# untitled.net
KiCad netlist of a schematic drawn in EAGLE
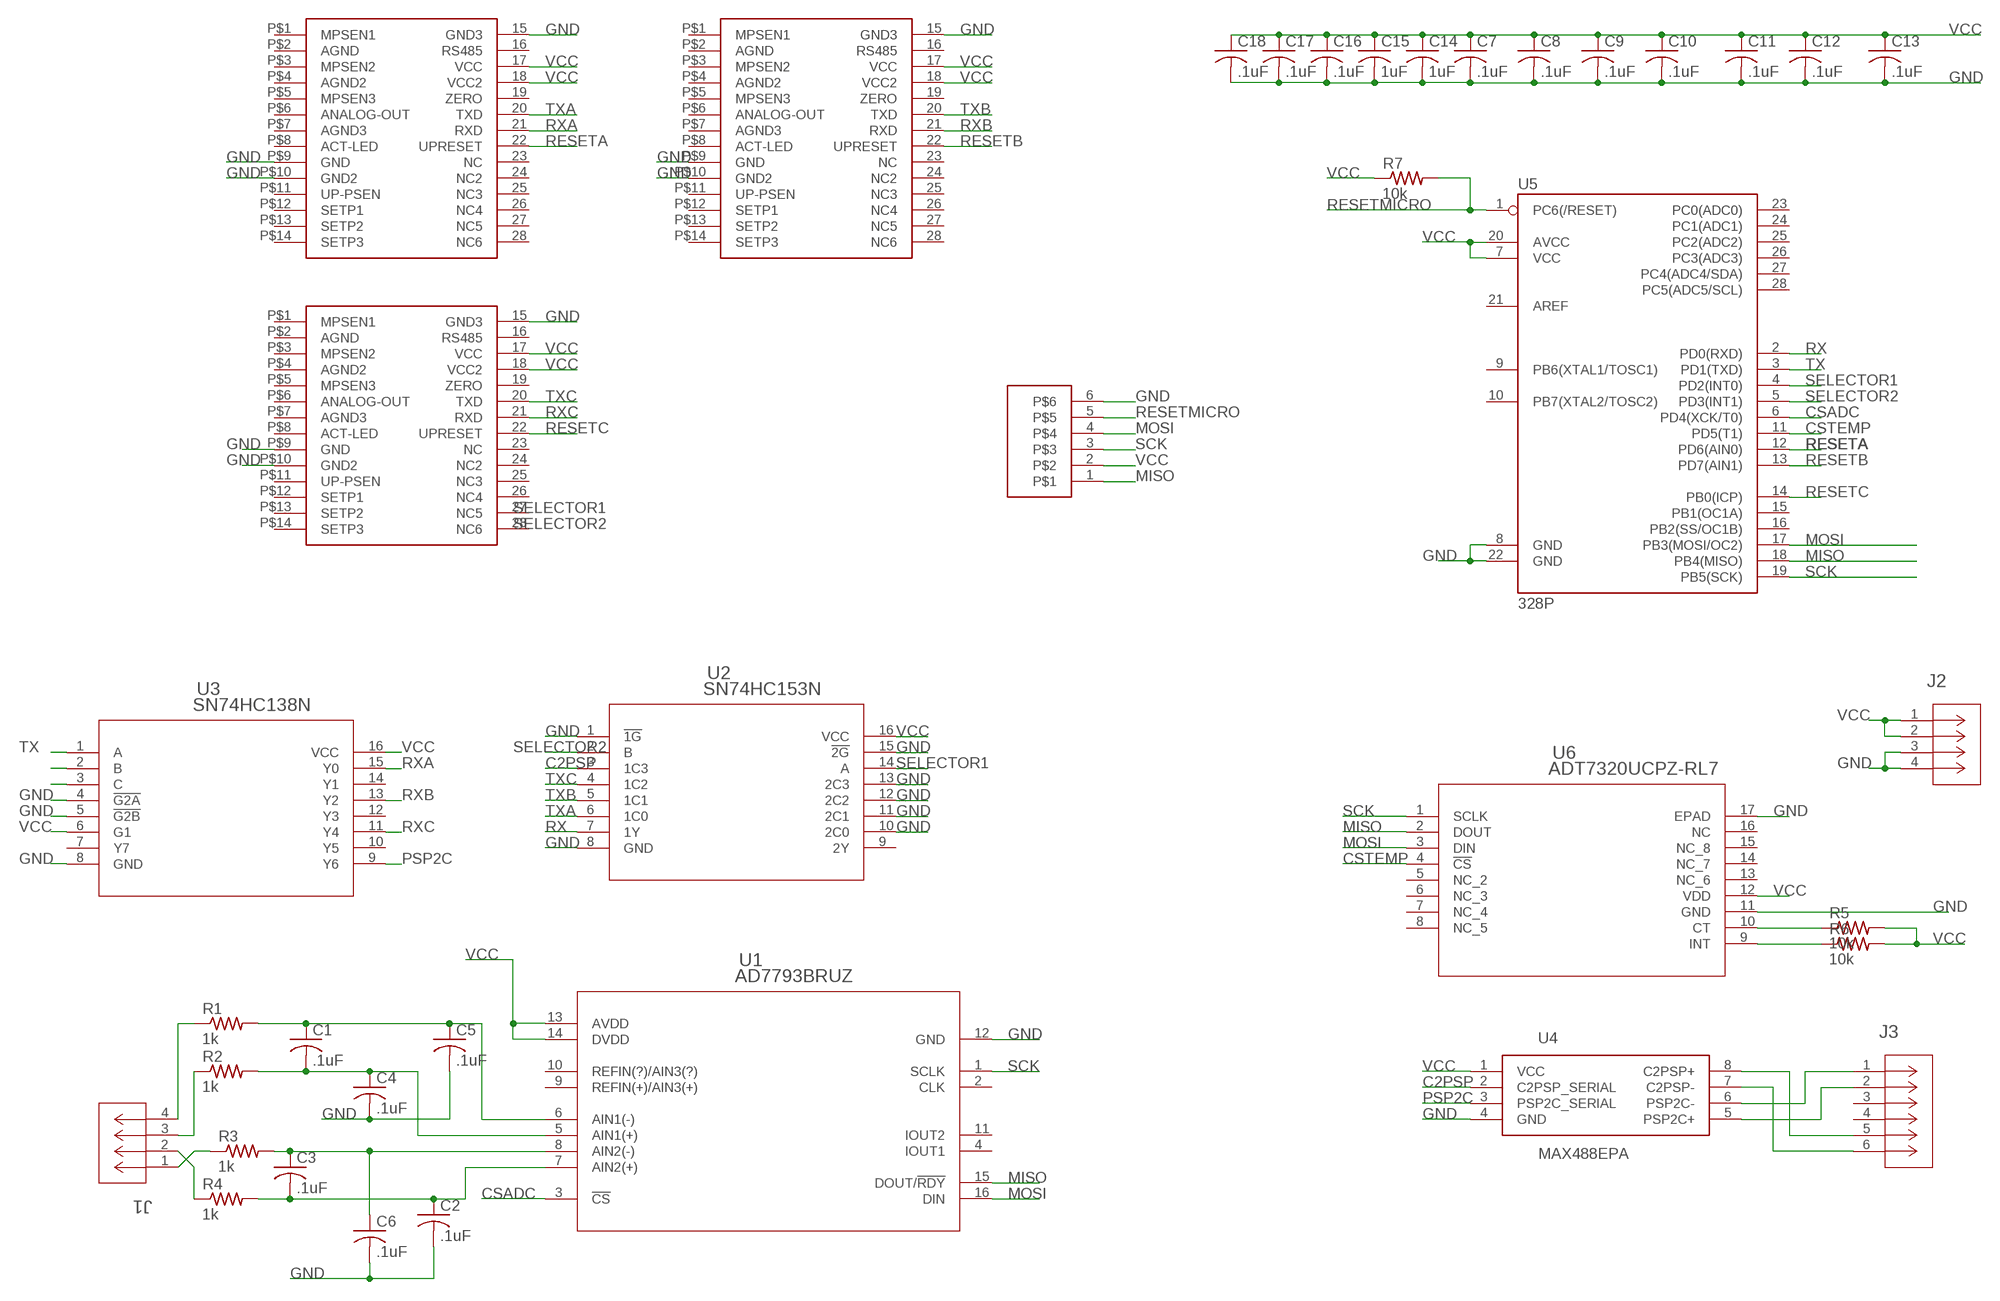
[diagram p0: schematic, sheet 1]

(export (version "E")
  (design (tool "Eeschema 10.0.6"))
  (components
    (comp (ref "C1")
      (value ".1uF")
      (footprint "eagle-import:C0603")
      (libsource (lib "eagle-import") (part "C-USC0603"))
    )
    (comp (ref "C2")
      (value ".1uF")
      (footprint "eagle-import:C0603")
      (libsource (lib "eagle-import") (part "C-USC0603"))
    )
    (comp (ref "C3")
      (value ".1uF")
      (footprint "eagle-import:C0603")
      (libsource (lib "eagle-import") (part "C-USC0603"))
    )
    (comp (ref "C4")
      (value ".1uF")
      (footprint "eagle-import:C0603")
      (libsource (lib "eagle-import") (part "C-USC0603"))
    )
    (comp (ref "C5")
      (value ".1uF")
      (footprint "eagle-import:C0603")
      (libsource (lib "eagle-import") (part "C-USC0603"))
    )
    (comp (ref "C6")
      (value ".1uF")
      (footprint "eagle-import:C0603")
      (libsource (lib "eagle-import") (part "C-USC0603"))
    )
    (comp (ref "C7")
      (value ".1uF")
      (footprint "eagle-import:C0603")
      (libsource (lib "eagle-import") (part "C-USC0603"))
    )
    (comp (ref "C8")
      (value ".1uF")
      (footprint "eagle-import:C0603")
      (libsource (lib "eagle-import") (part "C-USC0603"))
    )
    (comp (ref "C9")
      (value ".1uF")
      (footprint "eagle-import:C0603")
      (libsource (lib "eagle-import") (part "C-USC0603"))
    )
    (comp (ref "C10")
      (value ".1uF")
      (footprint "eagle-import:C0603")
      (libsource (lib "eagle-import") (part "C-USC0603"))
    )
    (comp (ref "C11")
      (value ".1uF")
      (footprint "eagle-import:C0603")
      (libsource (lib "eagle-import") (part "C-USC0603"))
    )
    (comp (ref "C12")
      (value ".1uF")
      (footprint "eagle-import:C0603")
      (libsource (lib "eagle-import") (part "C-USC0603"))
    )
    (comp (ref "C13")
      (value ".1uF")
      (footprint "eagle-import:C0603")
      (libsource (lib "eagle-import") (part "C-USC0603"))
    )
    (comp (ref "C14")
      (value "1uF")
      (footprint "eagle-import:C1206")
      (libsource (lib "eagle-import") (part "C-USC1206"))
    )
    (comp (ref "C15")
      (value "1uF")
      (footprint "eagle-import:C1206")
      (libsource (lib "eagle-import") (part "C-USC1206"))
    )
    (comp (ref "C16")
      (value ".1uF")
      (footprint "eagle-import:C0603")
      (libsource (lib "eagle-import") (part "C-USC0603"))
    )
    (comp (ref "C17")
      (value ".1uF")
      (footprint "eagle-import:C0603")
      (libsource (lib "eagle-import") (part "C-USC0603"))
    )
    (comp (ref "C18")
      (value ".1uF")
      (footprint "eagle-import:C0603")
      (libsource (lib "eagle-import") (part "C-USC0603"))
    )
    (comp (ref "J1")
      (value "DF11-4")
      (footprint "eagle-import:DF11-4")
      (libsource (lib "eagle-import") (part "DF11-4"))
    )
    (comp (ref "J2")
      (value "DF11-4")
      (footprint "eagle-import:DF11-4")
      (libsource (lib "eagle-import") (part "DF11-4"))
    )
    (comp (ref "J3")
      (value "DF11-6DP-2DSA(01)")
      (footprint "eagle-import:CON6_2X3_UF_DF11")
      (libsource (lib "eagle-import") (part "DF11-6DP-2DSA(01)"))
    )
    (comp (ref "R1")
      (value "1k")
      (footprint "eagle-import:R0603")
      (libsource (lib "eagle-import") (part "R-US_R0603"))
    )
    (comp (ref "R2")
      (value "1k")
      (footprint "eagle-import:R0603")
      (libsource (lib "eagle-import") (part "R-US_R0603"))
    )
    (comp (ref "R3")
      (value "1k")
      (footprint "eagle-import:R0603")
      (libsource (lib "eagle-import") (part "R-US_R0603"))
    )
    (comp (ref "R4")
      (value "1k")
      (footprint "eagle-import:R0603")
      (libsource (lib "eagle-import") (part "R-US_R0603"))
    )
    (comp (ref "R5")
      (value "10k")
      (footprint "eagle-import:R0603")
      (libsource (lib "eagle-import") (part "R-US_R0603"))
    )
    (comp (ref "R6")
      (value "10k")
      (footprint "eagle-import:R0603")
      (libsource (lib "eagle-import") (part "R-US_R0603"))
    )
    (comp (ref "R7")
      (value "10k")
      (footprint "eagle-import:R0603")
      (libsource (lib "eagle-import") (part "R-US_R0603"))
    )
    (comp (ref "U$1")
      (value "PROGRAMMER")
      (footprint "eagle-import:PROGRAMMER")
      (libsource (lib "eagle-import") (part "PROGRAMMER"))
    )
    (comp (ref "U$2")
      (value "MKS-PIRANI")
      (footprint "eagle-import:28PIN")
      (libsource (lib "eagle-import") (part "MKS-PIRANI"))
    )
    (comp (ref "U$3")
      (value "MKS-PIRANI")
      (footprint "eagle-import:28PIN")
      (libsource (lib "eagle-import") (part "MKS-PIRANI"))
    )
    (comp (ref "U$4")
      (value "MKS-PIRANI")
      (footprint "eagle-import:28PIN")
      (libsource (lib "eagle-import") (part "MKS-PIRANI"))
    )
    (comp (ref "U1")
      (value "AD7793BRUZ")
      (footprint "eagle-import:RU_16")
      (libsource (lib "eagle-import") (part "AD7793BRUZ"))
    )
    (comp (ref "U2")
      (value "SN74HC153N")
      (footprint "eagle-import:N16")
      (libsource (lib "eagle-import") (part "SN74HC153N"))
    )
    (comp (ref "U3")
      (value "SN74HC138N")
      (footprint "eagle-import:N16")
      (libsource (lib "eagle-import") (part "SN74HC138N"))
    )
    (comp (ref "U4")
      (value "MAX488EPA")
      (footprint "eagle-import:DIL08")
      (libsource (lib "eagle-import") (part "MAX488EPA"))
    )
    (comp (ref "U5")
      (value "328P")
      (footprint "eagle-import:DIP28")
      (libsource (lib "eagle-import") (part "ATMEGA328P_PDIP"))
    )
    (comp (ref "U6")
      (value "ADT7320UCPZ-RL7")
      (footprint "eagle-import:CP_16_17")
      (fields (field (name "MANUFACTURER_PART_NUMBER") "ADT7320UCPZRL7"))
      (libsource (lib "eagle-import") (part "ADT7320UCPZ-RL7"))
    )
  )
  (nets
    (net (code "1") (name "/C2PSP") (class "Default")
      (node (ref "U2") (pin "3") (pinfunction "1C3_3") (pintype "input"))
      (node (ref "U4") (pin "2") (pinfunction "C2PSP_SERIAL_2") (pintype "bidirectional"))
    )
    (net (code "2") (name "/CSADC") (class "Default")
      (node (ref "U1") (pin "3") (pinfunction "~{CS}_3") (pintype "input"))
      (node (ref "U5") (pin "6") (pinfunction "PD4(XCK/T0)_6") (pintype "bidirectional"))
    )
    (net (code "3") (name "/CSTEMP") (class "Default")
      (node (ref "U5") (pin "11") (pinfunction "PD5(T1)_11") (pintype "bidirectional"))
      (node (ref "U6") (pin "4") (pinfunction "~{CS}_4") (pintype "input"))
    )
    (net (code "4") (name "/GND") (class "Default")
      (node (ref "C10") (pin "2") (pinfunction "2_2") (pintype "passive"))
      (node (ref "C11") (pin "2") (pinfunction "2_2") (pintype "passive"))
      (node (ref "C12") (pin "2") (pinfunction "2_2") (pintype "passive"))
      (node (ref "C13") (pin "2") (pinfunction "2_2") (pintype "passive"))
      (node (ref "C14") (pin "2") (pinfunction "2_2") (pintype "passive"))
      (node (ref "C15") (pin "2") (pinfunction "2_2") (pintype "passive"))
      (node (ref "C16") (pin "2") (pinfunction "2_2") (pintype "passive"))
      (node (ref "C17") (pin "2") (pinfunction "2_2") (pintype "passive"))
      (node (ref "C18") (pin "2") (pinfunction "2_2") (pintype "passive"))
      (node (ref "C2") (pin "2") (pinfunction "2_2") (pintype "passive"))
      (node (ref "C4") (pin "2") (pinfunction "2_2") (pintype "passive"))
      (node (ref "C5") (pin "2") (pinfunction "2_2") (pintype "passive"))
      (node (ref "C6") (pin "2") (pinfunction "2_2") (pintype "passive"))
      (node (ref "C7") (pin "2") (pinfunction "2_2") (pintype "passive"))
      (node (ref "C8") (pin "2") (pinfunction "2_2") (pintype "passive"))
      (node (ref "C9") (pin "2") (pinfunction "2_2") (pintype "passive"))
      (node (ref "J2") (pin "3") (pinfunction "3_3") (pintype "passive"))
      (node (ref "J2") (pin "4") (pinfunction "4_4") (pintype "passive"))
      (node (ref "U$1") (pin "6") (pinfunction "P$6_6") (pintype "bidirectional"))
      (node (ref "U$2") (pin "15") (pinfunction "GND3_15") (pintype "bidirectional"))
      (node (ref "U$2") (pin "P$10") (pinfunction "GND2_P$10") (pintype "bidirectional"))
      (node (ref "U$2") (pin "P$9") (pinfunction "GND_P$9") (pintype "bidirectional"))
      (node (ref "U$3") (pin "15") (pinfunction "GND3_15") (pintype "bidirectional"))
      (node (ref "U$3") (pin "P$10") (pinfunction "GND2_P$10") (pintype "bidirectional"))
      (node (ref "U$3") (pin "P$9") (pinfunction "GND_P$9") (pintype "bidirectional"))
      (node (ref "U$4") (pin "15") (pinfunction "GND3_15") (pintype "bidirectional"))
      (node (ref "U$4") (pin "P$10") (pinfunction "GND2_P$10") (pintype "bidirectional"))
      (node (ref "U$4") (pin "P$9") (pinfunction "GND_P$9") (pintype "bidirectional"))
      (node (ref "U1") (pin "12") (pinfunction "GND_12") (pintype "passive"))
      (node (ref "U2") (pin "1") (pinfunction "~{1G}_1") (pintype "input"))
      (node (ref "U2") (pin "10") (pinfunction "2C0_10") (pintype "input"))
      (node (ref "U2") (pin "11") (pinfunction "2C1_11") (pintype "input"))
      (node (ref "U2") (pin "12") (pinfunction "2C2_12") (pintype "input"))
      (node (ref "U2") (pin "13") (pinfunction "2C3_13") (pintype "input"))
      (node (ref "U2") (pin "15") (pinfunction "~{2G}_15") (pintype "input"))
      (node (ref "U2") (pin "8") (pinfunction "GND_8") (pintype "power_in"))
      (node (ref "U3") (pin "4") (pinfunction "~{G2A}_4") (pintype "input"))
      (node (ref "U3") (pin "5") (pinfunction "~{G2B}_5") (pintype "input"))
      (node (ref "U3") (pin "8") (pinfunction "GND_8") (pintype "power_in"))
      (node (ref "U4") (pin "4") (pinfunction "GND_4") (pintype "bidirectional"))
      (node (ref "U5") (pin "22") (pinfunction "GND_22") (pintype "bidirectional"))
      (node (ref "U5") (pin "8") (pinfunction "GND_8") (pintype "bidirectional"))
      (node (ref "U6") (pin "11") (pinfunction "GND_11") (pintype "power_in"))
      (node (ref "U6") (pin "17") (pinfunction "EPAD_17") (pintype "passive"))
    )
    (net (code "5") (name "/MISO") (class "Default")
      (node (ref "U$1") (pin "1") (pinfunction "P$1_1") (pintype "bidirectional"))
      (node (ref "U1") (pin "15") (pinfunction "DOUT/~{RDY}_15") (pintype "output"))
      (node (ref "U5") (pin "18") (pinfunction "PB4(MISO)_18") (pintype "bidirectional"))
      (node (ref "U6") (pin "2") (pinfunction "DOUT_2") (pintype "output"))
    )
    (net (code "6") (name "/MOSI") (class "Default")
      (node (ref "U$1") (pin "4") (pinfunction "P$4_4") (pintype "bidirectional"))
      (node (ref "U1") (pin "16") (pinfunction "DIN_16") (pintype "input"))
      (node (ref "U5") (pin "17") (pinfunction "PB3(MOSI/OC2)_17") (pintype "bidirectional"))
      (node (ref "U6") (pin "3") (pinfunction "DIN_3") (pintype "input"))
    )
    (net (code "7") (name "/PSP2C") (class "Default")
      (node (ref "U3") (pin "9") (pinfunction "Y6_9") (pintype "output"))
      (node (ref "U4") (pin "3") (pinfunction "PSP2C_SERIAL_3") (pintype "bidirectional"))
    )
    (net (code "8") (name "/RESETA") (class "Default")
      (node (ref "U$2") (pin "22") (pinfunction "UPRESET_22") (pintype "bidirectional"))
      (node (ref "U5") (pin "12") (pinfunction "PD6(AIN0)_12") (pintype "bidirectional"))
    )
    (net (code "9") (name "/RESETB") (class "Default")
      (node (ref "U$4") (pin "22") (pinfunction "UPRESET_22") (pintype "bidirectional"))
      (node (ref "U5") (pin "13") (pinfunction "PD7(AIN1)_13") (pintype "bidirectional"))
    )
    (net (code "10") (name "/RESETC") (class "Default")
      (node (ref "U$3") (pin "22") (pinfunction "UPRESET_22") (pintype "bidirectional"))
      (node (ref "U5") (pin "14") (pinfunction "PB0(ICP)_14") (pintype "bidirectional"))
    )
    (net (code "11") (name "/RESETMICRO") (class "Default")
      (node (ref "R7") (pin "2") (pinfunction "2_2") (pintype "passive"))
      (node (ref "U$1") (pin "5") (pinfunction "P$5_5") (pintype "bidirectional"))
      (node (ref "U5") (pin "1") (pinfunction "PC6(/RESET)_1") (pintype "bidirectional"))
    )
    (net (code "12") (name "/RX") (class "Default")
      (node (ref "U2") (pin "7") (pinfunction "1Y_7") (pintype "passive"))
      (node (ref "U5") (pin "2") (pinfunction "PD0(RXD)_2") (pintype "bidirectional"))
    )
    (net (code "13") (name "/RXA") (class "Default")
      (node (ref "U$2") (pin "21") (pinfunction "RXD_21") (pintype "bidirectional"))
      (node (ref "U3") (pin "15") (pinfunction "Y0_15") (pintype "output"))
    )
    (net (code "14") (name "/RXB") (class "Default")
      (node (ref "U$4") (pin "21") (pinfunction "RXD_21") (pintype "bidirectional"))
      (node (ref "U3") (pin "13") (pinfunction "Y2_13") (pintype "output"))
    )
    (net (code "15") (name "/RXC") (class "Default")
      (node (ref "U$3") (pin "21") (pinfunction "RXD_21") (pintype "bidirectional"))
      (node (ref "U3") (pin "11") (pinfunction "Y4_11") (pintype "output"))
    )
    (net (code "16") (name "/SCK") (class "Default")
      (node (ref "U$1") (pin "3") (pinfunction "P$3_3") (pintype "bidirectional"))
      (node (ref "U1") (pin "1") (pinfunction "SCLK_1") (pintype "input"))
      (node (ref "U5") (pin "19") (pinfunction "PB5(SCK)_19") (pintype "bidirectional"))
      (node (ref "U6") (pin "1") (pinfunction "SCLK_1") (pintype "input"))
    )
    (net (code "17") (name "/SELECTOR1") (class "Default")
      (node (ref "U2") (pin "14") (pinfunction "A_14") (pintype "input"))
      (node (ref "U3") (pin "2") (pinfunction "B_2") (pintype "input"))
      (node (ref "U5") (pin "4") (pinfunction "PD2(INT0)_4") (pintype "bidirectional"))
    )
    (net (code "18") (name "/SELECTOR2") (class "Default")
      (node (ref "U2") (pin "2") (pinfunction "B_2") (pintype "input"))
      (node (ref "U3") (pin "3") (pinfunction "C_3") (pintype "input"))
      (node (ref "U5") (pin "5") (pinfunction "PD3(INT1)_5") (pintype "bidirectional"))
    )
    (net (code "19") (name "/TX") (class "Default")
      (node (ref "U3") (pin "1") (pinfunction "A_1") (pintype "input"))
      (node (ref "U5") (pin "3") (pinfunction "PD1(TXD)_3") (pintype "bidirectional"))
    )
    (net (code "20") (name "/TXA") (class "Default")
      (node (ref "U$2") (pin "20") (pinfunction "TXD_20") (pintype "bidirectional"))
      (node (ref "U2") (pin "6") (pinfunction "1C0_6") (pintype "input"))
    )
    (net (code "21") (name "/TXB") (class "Default")
      (node (ref "U$4") (pin "20") (pinfunction "TXD_20") (pintype "bidirectional"))
      (node (ref "U2") (pin "5") (pinfunction "1C1_5") (pintype "input"))
    )
    (net (code "22") (name "/TXC") (class "Default")
      (node (ref "U$3") (pin "20") (pinfunction "TXD_20") (pintype "bidirectional"))
      (node (ref "U2") (pin "4") (pinfunction "1C2_4") (pintype "input"))
    )
    (net (code "23") (name "/VCC") (class "Default")
      (node (ref "C10") (pin "1") (pinfunction "1_1") (pintype "passive"))
      (node (ref "C11") (pin "1") (pinfunction "1_1") (pintype "passive"))
      (node (ref "C12") (pin "1") (pinfunction "1_1") (pintype "passive"))
      (node (ref "C13") (pin "1") (pinfunction "1_1") (pintype "passive"))
      (node (ref "C14") (pin "1") (pinfunction "1_1") (pintype "passive"))
      (node (ref "C15") (pin "1") (pinfunction "1_1") (pintype "passive"))
      (node (ref "C16") (pin "1") (pinfunction "1_1") (pintype "passive"))
      (node (ref "C17") (pin "1") (pinfunction "1_1") (pintype "passive"))
      (node (ref "C18") (pin "1") (pinfunction "1_1") (pintype "passive"))
      (node (ref "C7") (pin "1") (pinfunction "1_1") (pintype "passive"))
      (node (ref "C8") (pin "1") (pinfunction "1_1") (pintype "passive"))
      (node (ref "C9") (pin "1") (pinfunction "1_1") (pintype "passive"))
      (node (ref "J2") (pin "1") (pinfunction "1_1") (pintype "passive"))
      (node (ref "J2") (pin "2") (pinfunction "2_2") (pintype "passive"))
      (node (ref "R5") (pin "2") (pinfunction "2_2") (pintype "passive"))
      (node (ref "R6") (pin "2") (pinfunction "2_2") (pintype "passive"))
      (node (ref "R7") (pin "1") (pinfunction "1_1") (pintype "passive"))
      (node (ref "U$1") (pin "2") (pinfunction "P$2_2") (pintype "bidirectional"))
      (node (ref "U$2") (pin "17") (pinfunction "VCC_17") (pintype "bidirectional"))
      (node (ref "U$2") (pin "18") (pinfunction "VCC2_18") (pintype "bidirectional"))
      (node (ref "U$3") (pin "17") (pinfunction "VCC_17") (pintype "bidirectional"))
      (node (ref "U$3") (pin "18") (pinfunction "VCC2_18") (pintype "bidirectional"))
      (node (ref "U$4") (pin "17") (pinfunction "VCC_17") (pintype "bidirectional"))
      (node (ref "U$4") (pin "18") (pinfunction "VCC2_18") (pintype "bidirectional"))
      (node (ref "U1") (pin "13") (pinfunction "AVDD_13") (pintype "power_in"))
      (node (ref "U1") (pin "14") (pinfunction "DVDD_14") (pintype "power_in"))
      (node (ref "U2") (pin "16") (pinfunction "VCC_16") (pintype "power_in"))
      (node (ref "U3") (pin "16") (pinfunction "VCC_16") (pintype "power_in"))
      (node (ref "U3") (pin "6") (pinfunction "G1_6") (pintype "input"))
      (node (ref "U4") (pin "1") (pinfunction "VCC_1") (pintype "bidirectional"))
      (node (ref "U5") (pin "20") (pinfunction "AVCC_20") (pintype "bidirectional"))
      (node (ref "U5") (pin "7") (pinfunction "VCC_7") (pintype "bidirectional"))
      (node (ref "U6") (pin "12") (pinfunction "VDD_12") (pintype "power_in"))
    )
    (net (code "24") (name "Net-(J1-Pad1)") (class "Default")
      (node (ref "J1") (pin "1") (pinfunction "1_1") (pintype "passive"))
      (node (ref "R3") (pin "1") (pinfunction "1_1") (pintype "passive"))
    )
    (net (code "25") (name "Net-(J1-Pad2)") (class "Default")
      (node (ref "J1") (pin "2") (pinfunction "2_2") (pintype "passive"))
      (node (ref "R4") (pin "1") (pinfunction "1_1") (pintype "passive"))
    )
    (net (code "26") (name "Net-(J1-Pad3)") (class "Default")
      (node (ref "J1") (pin "3") (pinfunction "3_3") (pintype "passive"))
      (node (ref "R2") (pin "1") (pinfunction "1_1") (pintype "passive"))
    )
    (net (code "27") (name "Net-(J1-Pad4)") (class "Default")
      (node (ref "J1") (pin "4") (pinfunction "4_4") (pintype "passive"))
      (node (ref "R1") (pin "1") (pinfunction "1_1") (pintype "passive"))
    )
    (net (code "28") (name "Net-(U1-AIN1(+))") (class "Default")
      (node (ref "C1") (pin "2") (pinfunction "2_2") (pintype "passive"))
      (node (ref "C4") (pin "1") (pinfunction "1_1") (pintype "passive"))
      (node (ref "R2") (pin "2") (pinfunction "2_2") (pintype "passive"))
      (node (ref "U1") (pin "5") (pinfunction "AIN1(+)_5") (pintype "input"))
    )
    (net (code "29") (name "Net-(U1-AIN1(-))") (class "Default")
      (node (ref "C1") (pin "1") (pinfunction "1_1") (pintype "passive"))
      (node (ref "C5") (pin "1") (pinfunction "1_1") (pintype "passive"))
      (node (ref "R1") (pin "2") (pinfunction "2_2") (pintype "passive"))
      (node (ref "U1") (pin "6") (pinfunction "AIN1(-)_6") (pintype "input"))
    )
    (net (code "30") (name "Net-(U1-AIN2(+))") (class "Default")
      (node (ref "C2") (pin "1") (pinfunction "1_1") (pintype "passive"))
      (node (ref "C3") (pin "2") (pinfunction "2_2") (pintype "passive"))
      (node (ref "R4") (pin "2") (pinfunction "2_2") (pintype "passive"))
      (node (ref "U1") (pin "7") (pinfunction "AIN2(+)_7") (pintype "input"))
    )
    (net (code "31") (name "Net-(U1-AIN2(-))") (class "Default")
      (node (ref "C3") (pin "1") (pinfunction "1_1") (pintype "passive"))
      (node (ref "C6") (pin "1") (pinfunction "1_1") (pintype "passive"))
      (node (ref "R3") (pin "2") (pinfunction "2_2") (pintype "passive"))
      (node (ref "U1") (pin "8") (pinfunction "AIN2(-)_8") (pintype "input"))
    )
    (net (code "32") (name "Net-(U4-C2PSP+)") (class "Default")
      (node (ref "J3") (pin "5") (pinfunction "5_5") (pintype "passive"))
      (node (ref "U4") (pin "8") (pinfunction "C2PSP+_8") (pintype "bidirectional"))
    )
    (net (code "33") (name "Net-(U4-C2PSP-)") (class "Default")
      (node (ref "J3") (pin "6") (pinfunction "6_6") (pintype "passive"))
      (node (ref "U4") (pin "7") (pinfunction "C2PSP-_7") (pintype "bidirectional"))
    )
    (net (code "34") (name "Net-(U4-PSP2C+)") (class "Default")
      (node (ref "J3") (pin "2") (pinfunction "2_2") (pintype "passive"))
      (node (ref "U4") (pin "5") (pinfunction "PSP2C+_5") (pintype "bidirectional"))
    )
    (net (code "35") (name "Net-(U4-PSP2C-)") (class "Default")
      (node (ref "J3") (pin "1") (pinfunction "1_1") (pintype "passive"))
      (node (ref "U4") (pin "6") (pinfunction "PSP2C-_6") (pintype "bidirectional"))
    )
    (net (code "36") (name "Net-(U6-CT)") (class "Default")
      (node (ref "R5") (pin "1") (pinfunction "1_1") (pintype "passive"))
      (node (ref "U6") (pin "10") (pinfunction "CT_10") (pintype "output"))
    )
    (net (code "37") (name "Net-(U6-INT)") (class "Default")
      (node (ref "R6") (pin "1") (pinfunction "1_1") (pintype "passive"))
      (node (ref "U6") (pin "9") (pinfunction "INT_9") (pintype "output"))
    )
    (net (code "38") (name "unconnected-(J3-Pad3)") (class "Default")
      (node (ref "J3") (pin "3") (pinfunction "3_3") (pintype "passive"))
    )
    (net (code "39") (name "unconnected-(J3-Pad4)") (class "Default")
      (node (ref "J3") (pin "4") (pinfunction "4_4") (pintype "passive"))
    )
    (net (code "40") (name "unconnected-(U$2-ACT-LED-PadP$8)") (class "Default")
      (node (ref "U$2") (pin "P$8") (pinfunction "ACT-LED_P$8") (pintype "bidirectional"))
    )
    (net (code "41") (name "unconnected-(U$2-AGND-PadP$2)") (class "Default")
      (node (ref "U$2") (pin "P$2") (pinfunction "AGND_P$2") (pintype "bidirectional"))
    )
    (net (code "42") (name "unconnected-(U$2-AGND2-PadP$4)") (class "Default")
      (node (ref "U$2") (pin "P$4") (pinfunction "AGND2_P$4") (pintype "bidirectional"))
    )
    (net (code "43") (name "unconnected-(U$2-AGND3-PadP$7)") (class "Default")
      (node (ref "U$2") (pin "P$7") (pinfunction "AGND3_P$7") (pintype "bidirectional"))
    )
    (net (code "44") (name "unconnected-(U$2-ANALOG-OUT-PadP$6)") (class "Default")
      (node (ref "U$2") (pin "P$6") (pinfunction "ANALOG-OUT_P$6") (pintype "bidirectional"))
    )
    (net (code "45") (name "unconnected-(U$2-MPSEN1-PadP$1)") (class "Default")
      (node (ref "U$2") (pin "P$1") (pinfunction "MPSEN1_P$1") (pintype "bidirectional"))
    )
    (net (code "46") (name "unconnected-(U$2-MPSEN2-PadP$3)") (class "Default")
      (node (ref "U$2") (pin "P$3") (pinfunction "MPSEN2_P$3") (pintype "bidirectional"))
    )
    (net (code "47") (name "unconnected-(U$2-MPSEN3-PadP$5)") (class "Default")
      (node (ref "U$2") (pin "P$5") (pinfunction "MPSEN3_P$5") (pintype "bidirectional"))
    )
    (net (code "48") (name "unconnected-(U$2-NC-Pad23)") (class "Default")
      (node (ref "U$2") (pin "23") (pinfunction "NC_23") (pintype "bidirectional"))
    )
    (net (code "49") (name "unconnected-(U$2-NC2-Pad24)") (class "Default")
      (node (ref "U$2") (pin "24") (pinfunction "NC2_24") (pintype "bidirectional"))
    )
    (net (code "50") (name "unconnected-(U$2-NC3-Pad25)") (class "Default")
      (node (ref "U$2") (pin "25") (pinfunction "NC3_25") (pintype "bidirectional"))
    )
    (net (code "51") (name "unconnected-(U$2-NC4-Pad26)") (class "Default")
      (node (ref "U$2") (pin "26") (pinfunction "NC4_26") (pintype "bidirectional"))
    )
    (net (code "52") (name "unconnected-(U$2-NC5-Pad27)") (class "Default")
      (node (ref "U$2") (pin "27") (pinfunction "NC5_27") (pintype "bidirectional"))
    )
    (net (code "53") (name "unconnected-(U$2-NC6-Pad28)") (class "Default")
      (node (ref "U$2") (pin "28") (pinfunction "NC6_28") (pintype "bidirectional"))
    )
    (net (code "54") (name "unconnected-(U$2-RS485-Pad16)") (class "Default")
      (node (ref "U$2") (pin "16") (pinfunction "RS485_16") (pintype "bidirectional"))
    )
    (net (code "55") (name "unconnected-(U$2-SETP1-PadP$12)") (class "Default")
      (node (ref "U$2") (pin "P$12") (pinfunction "SETP1_P$12") (pintype "bidirectional"))
    )
    (net (code "56") (name "unconnected-(U$2-SETP2-PadP$13)") (class "Default")
      (node (ref "U$2") (pin "P$13") (pinfunction "SETP2_P$13") (pintype "bidirectional"))
    )
    (net (code "57") (name "unconnected-(U$2-SETP3-PadP$14)") (class "Default")
      (node (ref "U$2") (pin "P$14") (pinfunction "SETP3_P$14") (pintype "bidirectional"))
    )
    (net (code "58") (name "unconnected-(U$2-UP-PSEN-PadP$11)") (class "Default")
      (node (ref "U$2") (pin "P$11") (pinfunction "UP-PSEN_P$11") (pintype "bidirectional"))
    )
    (net (code "59") (name "unconnected-(U$2-ZERO-Pad19)") (class "Default")
      (node (ref "U$2") (pin "19") (pinfunction "ZERO_19") (pintype "bidirectional"))
    )
    (net (code "60") (name "unconnected-(U$3-ACT-LED-PadP$8)") (class "Default")
      (node (ref "U$3") (pin "P$8") (pinfunction "ACT-LED_P$8") (pintype "bidirectional"))
    )
    (net (code "61") (name "unconnected-(U$3-AGND-PadP$2)") (class "Default")
      (node (ref "U$3") (pin "P$2") (pinfunction "AGND_P$2") (pintype "bidirectional"))
    )
    (net (code "62") (name "unconnected-(U$3-AGND2-PadP$4)") (class "Default")
      (node (ref "U$3") (pin "P$4") (pinfunction "AGND2_P$4") (pintype "bidirectional"))
    )
    (net (code "63") (name "unconnected-(U$3-AGND3-PadP$7)") (class "Default")
      (node (ref "U$3") (pin "P$7") (pinfunction "AGND3_P$7") (pintype "bidirectional"))
    )
    (net (code "64") (name "unconnected-(U$3-ANALOG-OUT-PadP$6)") (class "Default")
      (node (ref "U$3") (pin "P$6") (pinfunction "ANALOG-OUT_P$6") (pintype "bidirectional"))
    )
    (net (code "65") (name "unconnected-(U$3-MPSEN1-PadP$1)") (class "Default")
      (node (ref "U$3") (pin "P$1") (pinfunction "MPSEN1_P$1") (pintype "bidirectional"))
    )
    (net (code "66") (name "unconnected-(U$3-MPSEN2-PadP$3)") (class "Default")
      (node (ref "U$3") (pin "P$3") (pinfunction "MPSEN2_P$3") (pintype "bidirectional"))
    )
    (net (code "67") (name "unconnected-(U$3-MPSEN3-PadP$5)") (class "Default")
      (node (ref "U$3") (pin "P$5") (pinfunction "MPSEN3_P$5") (pintype "bidirectional"))
    )
    (net (code "68") (name "unconnected-(U$3-NC-Pad23)") (class "Default")
      (node (ref "U$3") (pin "23") (pinfunction "NC_23") (pintype "bidirectional"))
    )
    (net (code "69") (name "unconnected-(U$3-NC2-Pad24)") (class "Default")
      (node (ref "U$3") (pin "24") (pinfunction "NC2_24") (pintype "bidirectional"))
    )
    (net (code "70") (name "unconnected-(U$3-NC3-Pad25)") (class "Default")
      (node (ref "U$3") (pin "25") (pinfunction "NC3_25") (pintype "bidirectional"))
    )
    (net (code "71") (name "unconnected-(U$3-NC4-Pad26)") (class "Default")
      (node (ref "U$3") (pin "26") (pinfunction "NC4_26") (pintype "bidirectional"))
    )
    (net (code "72") (name "unconnected-(U$3-NC5-Pad27)") (class "Default")
      (node (ref "U$3") (pin "27") (pinfunction "NC5_27") (pintype "bidirectional"))
    )
    (net (code "73") (name "unconnected-(U$3-NC6-Pad28)") (class "Default")
      (node (ref "U$3") (pin "28") (pinfunction "NC6_28") (pintype "bidirectional"))
    )
    (net (code "74") (name "unconnected-(U$3-RS485-Pad16)") (class "Default")
      (node (ref "U$3") (pin "16") (pinfunction "RS485_16") (pintype "bidirectional"))
    )
    (net (code "75") (name "unconnected-(U$3-SETP1-PadP$12)") (class "Default")
      (node (ref "U$3") (pin "P$12") (pinfunction "SETP1_P$12") (pintype "bidirectional"))
    )
    (net (code "76") (name "unconnected-(U$3-SETP2-PadP$13)") (class "Default")
      (node (ref "U$3") (pin "P$13") (pinfunction "SETP2_P$13") (pintype "bidirectional"))
    )
    (net (code "77") (name "unconnected-(U$3-SETP3-PadP$14)") (class "Default")
      (node (ref "U$3") (pin "P$14") (pinfunction "SETP3_P$14") (pintype "bidirectional"))
    )
    (net (code "78") (name "unconnected-(U$3-UP-PSEN-PadP$11)") (class "Default")
      (node (ref "U$3") (pin "P$11") (pinfunction "UP-PSEN_P$11") (pintype "bidirectional"))
    )
    (net (code "79") (name "unconnected-(U$3-ZERO-Pad19)") (class "Default")
      (node (ref "U$3") (pin "19") (pinfunction "ZERO_19") (pintype "bidirectional"))
    )
    (net (code "80") (name "unconnected-(U$4-ACT-LED-PadP$8)") (class "Default")
      (node (ref "U$4") (pin "P$8") (pinfunction "ACT-LED_P$8") (pintype "bidirectional"))
    )
    (net (code "81") (name "unconnected-(U$4-AGND-PadP$2)") (class "Default")
      (node (ref "U$4") (pin "P$2") (pinfunction "AGND_P$2") (pintype "bidirectional"))
    )
    (net (code "82") (name "unconnected-(U$4-AGND2-PadP$4)") (class "Default")
      (node (ref "U$4") (pin "P$4") (pinfunction "AGND2_P$4") (pintype "bidirectional"))
    )
    (net (code "83") (name "unconnected-(U$4-AGND3-PadP$7)") (class "Default")
      (node (ref "U$4") (pin "P$7") (pinfunction "AGND3_P$7") (pintype "bidirectional"))
    )
    (net (code "84") (name "unconnected-(U$4-ANALOG-OUT-PadP$6)") (class "Default")
      (node (ref "U$4") (pin "P$6") (pinfunction "ANALOG-OUT_P$6") (pintype "bidirectional"))
    )
    (net (code "85") (name "unconnected-(U$4-MPSEN1-PadP$1)") (class "Default")
      (node (ref "U$4") (pin "P$1") (pinfunction "MPSEN1_P$1") (pintype "bidirectional"))
    )
    (net (code "86") (name "unconnected-(U$4-MPSEN2-PadP$3)") (class "Default")
      (node (ref "U$4") (pin "P$3") (pinfunction "MPSEN2_P$3") (pintype "bidirectional"))
    )
    (net (code "87") (name "unconnected-(U$4-MPSEN3-PadP$5)") (class "Default")
      (node (ref "U$4") (pin "P$5") (pinfunction "MPSEN3_P$5") (pintype "bidirectional"))
    )
    (net (code "88") (name "unconnected-(U$4-NC-Pad23)") (class "Default")
      (node (ref "U$4") (pin "23") (pinfunction "NC_23") (pintype "bidirectional"))
    )
    (net (code "89") (name "unconnected-(U$4-NC2-Pad24)") (class "Default")
      (node (ref "U$4") (pin "24") (pinfunction "NC2_24") (pintype "bidirectional"))
    )
    (net (code "90") (name "unconnected-(U$4-NC3-Pad25)") (class "Default")
      (node (ref "U$4") (pin "25") (pinfunction "NC3_25") (pintype "bidirectional"))
    )
    (net (code "91") (name "unconnected-(U$4-NC4-Pad26)") (class "Default")
      (node (ref "U$4") (pin "26") (pinfunction "NC4_26") (pintype "bidirectional"))
    )
    (net (code "92") (name "unconnected-(U$4-NC5-Pad27)") (class "Default")
      (node (ref "U$4") (pin "27") (pinfunction "NC5_27") (pintype "bidirectional"))
    )
    (net (code "93") (name "unconnected-(U$4-NC6-Pad28)") (class "Default")
      (node (ref "U$4") (pin "28") (pinfunction "NC6_28") (pintype "bidirectional"))
    )
    (net (code "94") (name "unconnected-(U$4-RS485-Pad16)") (class "Default")
      (node (ref "U$4") (pin "16") (pinfunction "RS485_16") (pintype "bidirectional"))
    )
    (net (code "95") (name "unconnected-(U$4-SETP1-PadP$12)") (class "Default")
      (node (ref "U$4") (pin "P$12") (pinfunction "SETP1_P$12") (pintype "bidirectional"))
    )
    (net (code "96") (name "unconnected-(U$4-SETP2-PadP$13)") (class "Default")
      (node (ref "U$4") (pin "P$13") (pinfunction "SETP2_P$13") (pintype "bidirectional"))
    )
    (net (code "97") (name "unconnected-(U$4-SETP3-PadP$14)") (class "Default")
      (node (ref "U$4") (pin "P$14") (pinfunction "SETP3_P$14") (pintype "bidirectional"))
    )
    (net (code "98") (name "unconnected-(U$4-UP-PSEN-PadP$11)") (class "Default")
      (node (ref "U$4") (pin "P$11") (pinfunction "UP-PSEN_P$11") (pintype "bidirectional"))
    )
    (net (code "99") (name "unconnected-(U$4-ZERO-Pad19)") (class "Default")
      (node (ref "U$4") (pin "19") (pinfunction "ZERO_19") (pintype "bidirectional"))
    )
    (net (code "100") (name "unconnected-(U1-CLK-Pad2)") (class "Default")
      (node (ref "U1") (pin "2") (pinfunction "CLK_2") (pintype "passive"))
    )
    (net (code "101") (name "unconnected-(U1-IOUT1-Pad4)") (class "Default")
      (node (ref "U1") (pin "4") (pinfunction "IOUT1_4") (pintype "output"))
    )
    (net (code "102") (name "unconnected-(U1-IOUT2-Pad11)") (class "Default")
      (node (ref "U1") (pin "11") (pinfunction "IOUT2_11") (pintype "output"))
    )
    (net (code "103") (name "unconnected-(U1-REFIN(+){slash}AIN3(+)-Pad9)") (class "Default")
      (node (ref "U1") (pin "9") (pinfunction "REFIN(+)/AIN3(+)_9") (pintype "input"))
    )
    (net (code "104") (name "unconnected-(U1-REFIN(?){slash}AIN3(?)-Pad10)") (class "Default")
      (node (ref "U1") (pin "10") (pinfunction "REFIN(?)/AIN3(?)_10") (pintype "input"))
    )
    (net (code "105") (name "unconnected-(U2-2Y-Pad9)") (class "Default")
      (node (ref "U2") (pin "9") (pinfunction "2Y_9") (pintype "passive"))
    )
    (net (code "106") (name "unconnected-(U3-Y1-Pad14)") (class "Default")
      (node (ref "U3") (pin "14") (pinfunction "Y1_14") (pintype "output"))
    )
    (net (code "107") (name "unconnected-(U3-Y3-Pad12)") (class "Default")
      (node (ref "U3") (pin "12") (pinfunction "Y3_12") (pintype "output"))
    )
    (net (code "108") (name "unconnected-(U3-Y5-Pad10)") (class "Default")
      (node (ref "U3") (pin "10") (pinfunction "Y5_10") (pintype "output"))
    )
    (net (code "109") (name "unconnected-(U3-Y7-Pad7)") (class "Default")
      (node (ref "U3") (pin "7") (pinfunction "Y7_7") (pintype "output"))
    )
    (net (code "110") (name "unconnected-(U5-AREF-Pad21)") (class "Default")
      (node (ref "U5") (pin "21") (pinfunction "AREF_21") (pintype "bidirectional"))
    )
    (net (code "111") (name "unconnected-(U5-PB1(OC1A)-Pad15)") (class "Default")
      (node (ref "U5") (pin "15") (pinfunction "PB1(OC1A)_15") (pintype "bidirectional"))
    )
    (net (code "112") (name "unconnected-(U5-PB2(SS{slash}OC1B)-Pad16)") (class "Default")
      (node (ref "U5") (pin "16") (pinfunction "PB2(SS/OC1B)_16") (pintype "bidirectional"))
    )
    (net (code "113") (name "unconnected-(U5-PB6(XTAL1{slash}TOSC1)-Pad9)") (class "Default")
      (node (ref "U5") (pin "9") (pinfunction "PB6(XTAL1/TOSC1)_9") (pintype "bidirectional"))
    )
    (net (code "114") (name "unconnected-(U5-PB7(XTAL2{slash}TOSC2)-Pad10)") (class "Default")
      (node (ref "U5") (pin "10") (pinfunction "PB7(XTAL2/TOSC2)_10") (pintype "bidirectional"))
    )
    (net (code "115") (name "unconnected-(U5-PC0(ADC0)-Pad23)") (class "Default")
      (node (ref "U5") (pin "23") (pinfunction "PC0(ADC0)_23") (pintype "bidirectional"))
    )
    (net (code "116") (name "unconnected-(U5-PC1(ADC1)-Pad24)") (class "Default")
      (node (ref "U5") (pin "24") (pinfunction "PC1(ADC1)_24") (pintype "bidirectional"))
    )
    (net (code "117") (name "unconnected-(U5-PC2(ADC2)-Pad25)") (class "Default")
      (node (ref "U5") (pin "25") (pinfunction "PC2(ADC2)_25") (pintype "bidirectional"))
    )
    (net (code "118") (name "unconnected-(U5-PC3(ADC3)-Pad26)") (class "Default")
      (node (ref "U5") (pin "26") (pinfunction "PC3(ADC3)_26") (pintype "bidirectional"))
    )
    (net (code "119") (name "unconnected-(U5-PC4(ADC4{slash}SDA)-Pad27)") (class "Default")
      (node (ref "U5") (pin "27") (pinfunction "PC4(ADC4/SDA)_27") (pintype "bidirectional"))
    )
    (net (code "120") (name "unconnected-(U5-PC5(ADC5{slash}SCL)-Pad28)") (class "Default")
      (node (ref "U5") (pin "28") (pinfunction "PC5(ADC5/SCL)_28") (pintype "bidirectional"))
    )
    (net (code "121") (name "unconnected-(U6-NC-Pad16)") (class "Default")
      (node (ref "U6") (pin "16") (pinfunction "NC_16") (pintype "no_connect"))
    )
    (net (code "122") (name "unconnected-(U6-NC_2-Pad5)") (class "Default")
      (node (ref "U6") (pin "5") (pinfunction "NC_2_5") (pintype "no_connect"))
    )
    (net (code "123") (name "unconnected-(U6-NC_3-Pad6)") (class "Default")
      (node (ref "U6") (pin "6") (pinfunction "NC_3_6") (pintype "no_connect"))
    )
    (net (code "124") (name "unconnected-(U6-NC_4-Pad7)") (class "Default")
      (node (ref "U6") (pin "7") (pinfunction "NC_4_7") (pintype "no_connect"))
    )
    (net (code "125") (name "unconnected-(U6-NC_5-Pad8)") (class "Default")
      (node (ref "U6") (pin "8") (pinfunction "NC_5_8") (pintype "no_connect"))
    )
    (net (code "126") (name "unconnected-(U6-NC_6-Pad13)") (class "Default")
      (node (ref "U6") (pin "13") (pinfunction "NC_6_13") (pintype "no_connect"))
    )
    (net (code "127") (name "unconnected-(U6-NC_7-Pad14)") (class "Default")
      (node (ref "U6") (pin "14") (pinfunction "NC_7_14") (pintype "no_connect"))
    )
    (net (code "128") (name "unconnected-(U6-NC_8-Pad15)") (class "Default")
      (node (ref "U6") (pin "15") (pinfunction "NC_8_15") (pintype "no_connect"))
    )
  )
)
